# Multivibrator_2_0.net
KiCad netlist of a schematic drawn in EasyEDA
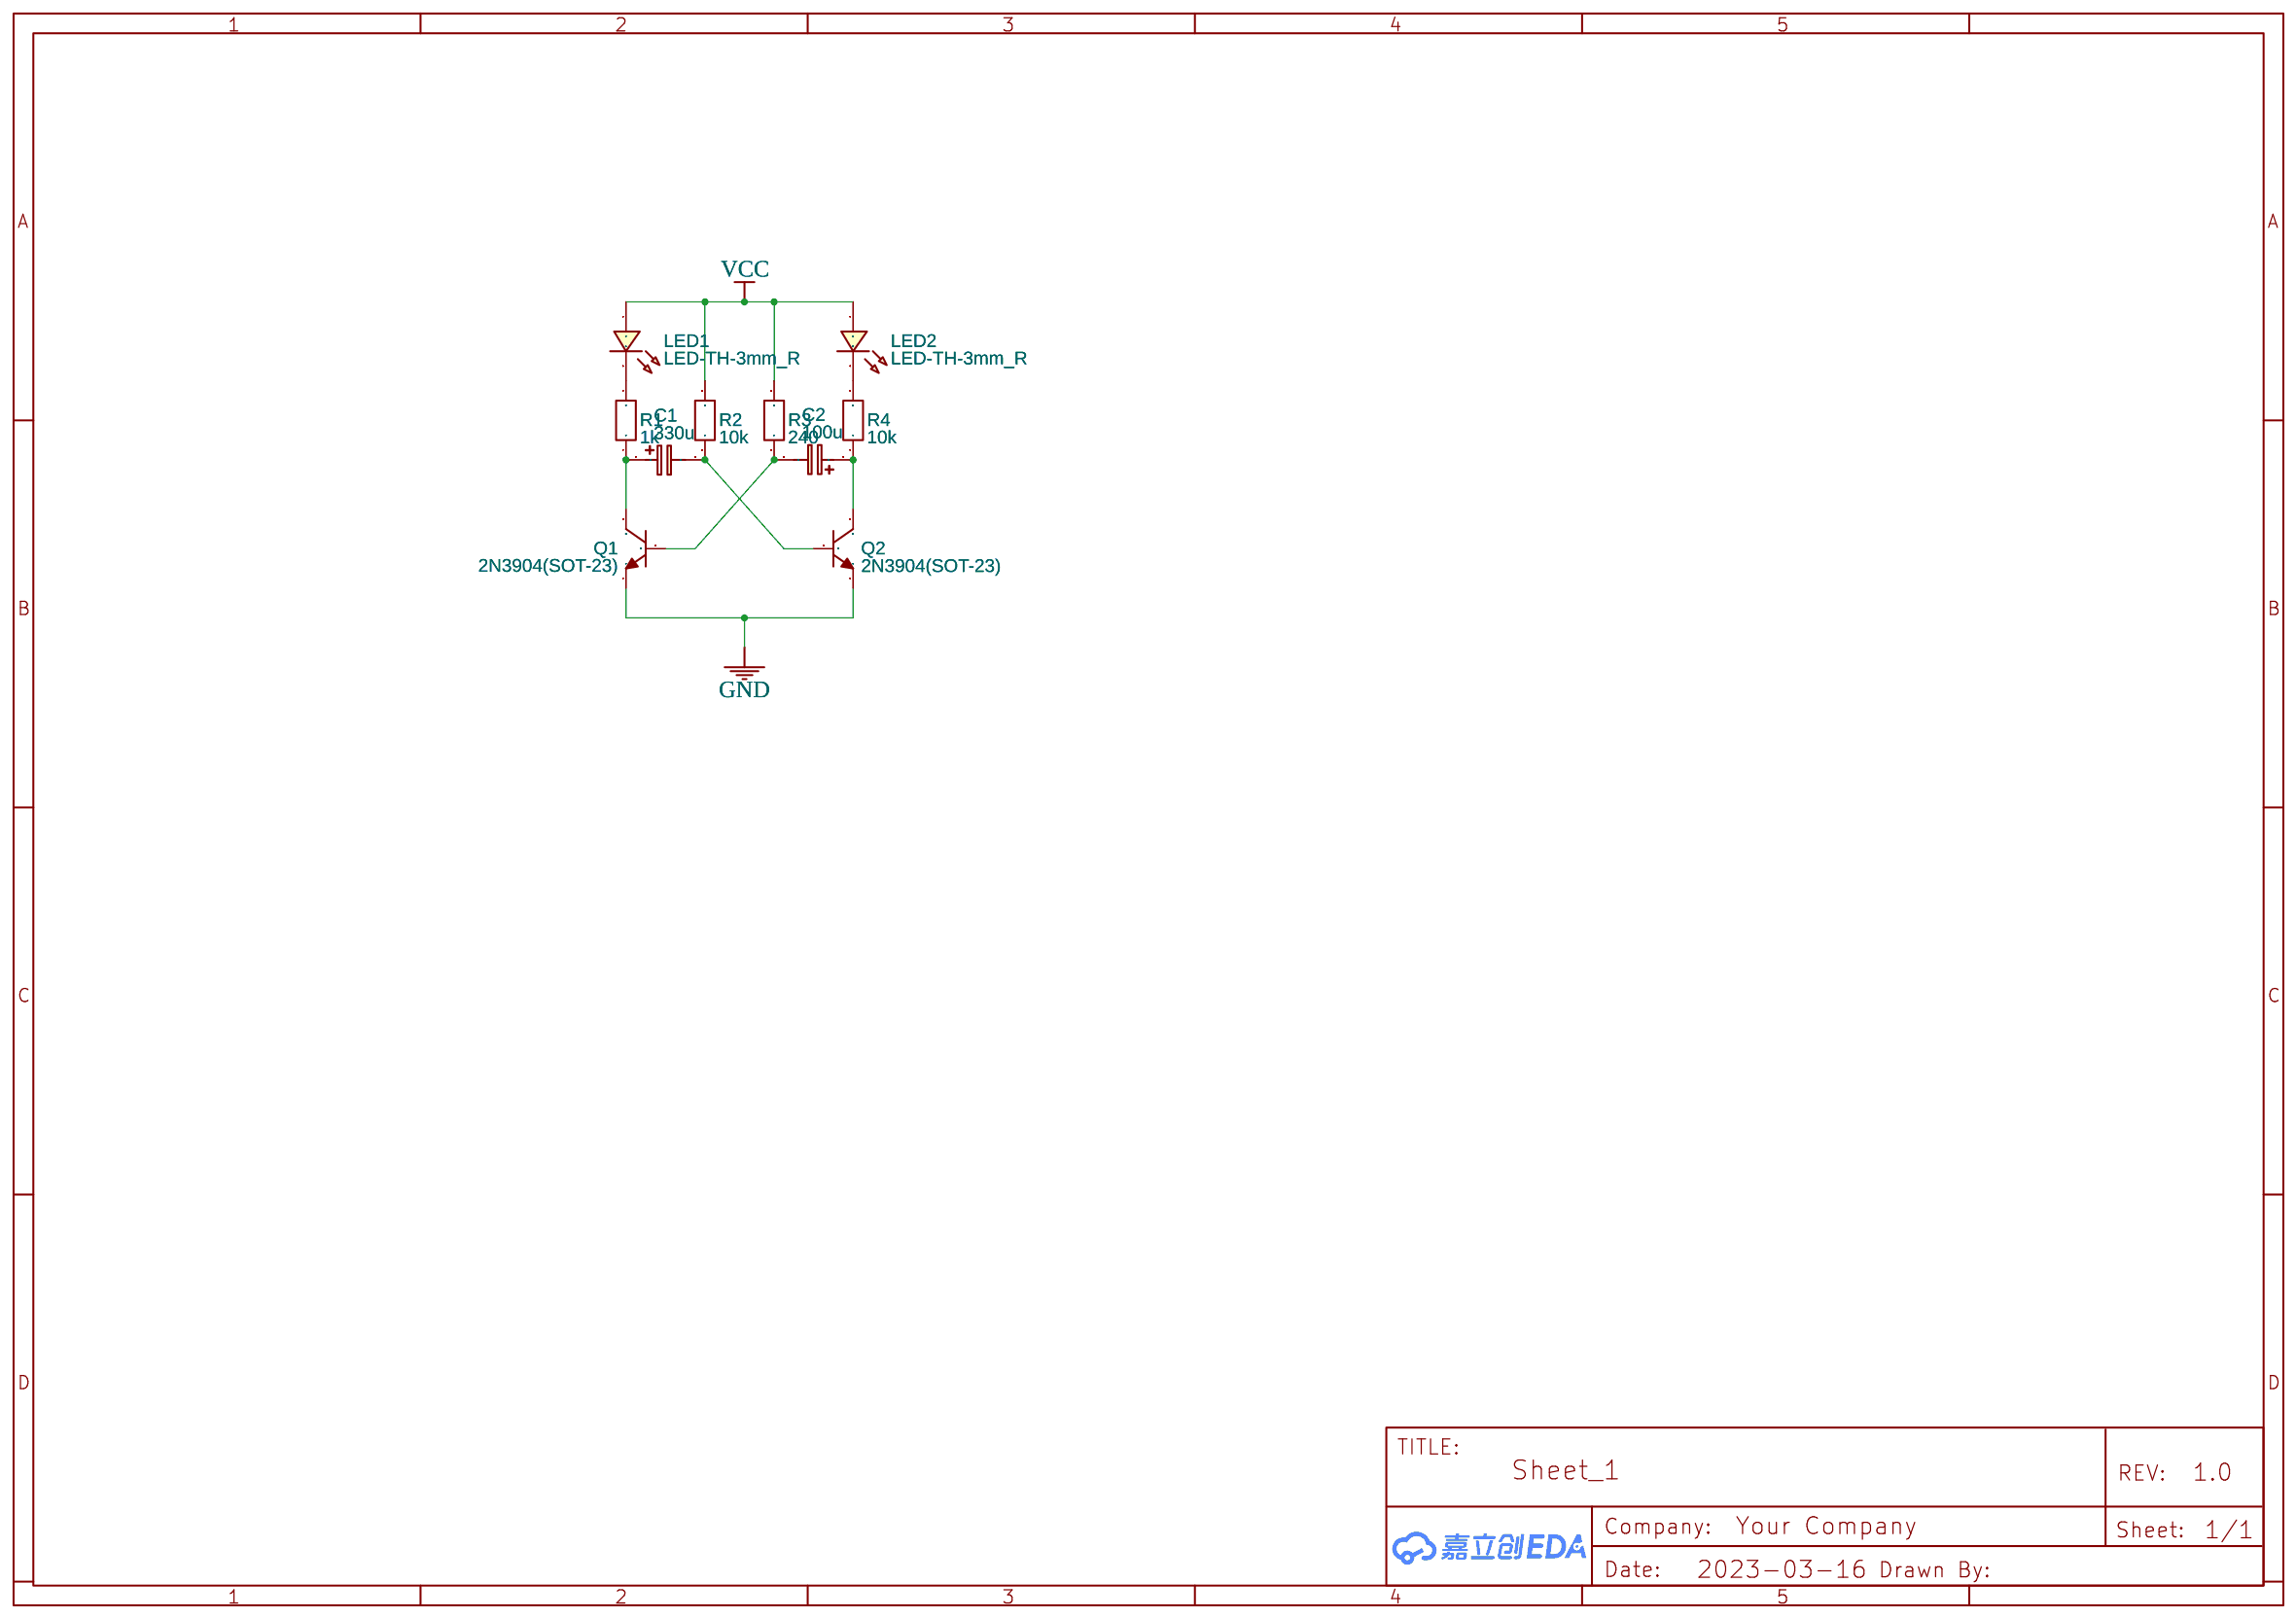
[diagram p0: schematic sheet]

(export (version "E")
  (design (tool "Eeschema 10.0.6"))
  (components
    (comp (ref "C1") (value "330u") (libsource (lib "") (part "CE_TH_D3.0×F1.5_EU")))
    (comp (ref "C2") (value "100u") (libsource (lib "") (part "CE_TH_D3.0×F1.5_EU_1")))
    (comp (ref "LED1")
      (value "LED-TH-3mm_R")
      (fields
        (field (name "BOM_Manufacturer Part") "204-10SDRD/S530-A3-L")
        (field (name "BOM_Supplier Part") "C84774")
      )
      (libsource (lib "") (part "LED-TH-3mm_R"))
    )
    (comp (ref "LED2")
      (value "LED-TH-3mm_R")
      (fields
        (field (name "BOM_Manufacturer Part") "204-10SDRD/S530-A3-L")
        (field (name "BOM_Supplier Part") "C84774")
      )
      (libsource (lib "") (part "LED-TH-3mm_R"))
    )
    (comp (ref "Q1")
      (value "2N3904(SOT-23)")
      (fields
        (field (name "BOM_Manufacturer Part") "2n3904S-RTK/PS")
        (field (name "BOM_Supplier Part") "C18536")
      )
      (libsource (lib "") (part "2N3904(SOT-23)"))
    )
    (comp (ref "Q2")
      (value "2N3904(SOT-23)")
      (fields
        (field (name "BOM_Manufacturer Part") "2n3904S-RTK/PS")
        (field (name "BOM_Supplier Part") "C18536")
      )
      (libsource (lib "") (part "2N3904(SOT-23)_1"))
    )
    (comp (ref "R1") (value "1k") (libsource (lib "") (part "R_AXIAL-0.3_EU")))
    (comp (ref "R2") (value "10k") (libsource (lib "") (part "R_AXIAL-0.3_EU")))
    (comp (ref "R3") (value "240") (libsource (lib "") (part "R_AXIAL-0.3_EU")))
    (comp (ref "R4") (value "10k") (libsource (lib "") (part "R_AXIAL-0.3_EU")))
  )
  (nets
    (net (code "1") (name "GND") (class "Default")
      (node (ref "Q1") (pin "1") (pinfunction "E_1") (pintype "input"))
      (node (ref "Q2") (pin "1") (pinfunction "E_1") (pintype "input"))
    )
    (net (code "2") (name "Net-(LED1-Pad2)") (class "Default")
      (node (ref "LED1") (pin "2") (pinfunction "2_2") (pintype "unspecified"))
      (node (ref "R1") (pin "2") (pinfunction "2_2") (pintype "unspecified"))
    )
    (net (code "3") (name "Net-(LED2-Pad2)") (class "Default")
      (node (ref "LED2") (pin "2") (pinfunction "2_2") (pintype "unspecified"))
      (node (ref "R4") (pin "2") (pinfunction "2_2") (pintype "unspecified"))
    )
    (net (code "4") (name "Net-(Q1-B)") (class "Default")
      (node (ref "C2") (pin "2") (pinfunction "2_2") (pintype "unspecified"))
      (node (ref "Q1") (pin "2") (pinfunction "B_2") (pintype "input"))
      (node (ref "R3") (pin "1") (pinfunction "1_1") (pintype "unspecified"))
    )
    (net (code "5") (name "Net-(Q1-C)") (class "Default")
      (node (ref "C1") (pin "1") (pinfunction "1_1") (pintype "unspecified"))
      (node (ref "Q1") (pin "3") (pinfunction "C_3") (pintype "input"))
      (node (ref "R1") (pin "1") (pinfunction "1_1") (pintype "unspecified"))
    )
    (net (code "6") (name "Net-(Q2-B)") (class "Default")
      (node (ref "C1") (pin "2") (pinfunction "2_2") (pintype "unspecified"))
      (node (ref "Q2") (pin "2") (pinfunction "B_2") (pintype "input"))
      (node (ref "R2") (pin "1") (pinfunction "1_1") (pintype "unspecified"))
    )
    (net (code "7") (name "Net-(Q2-C)") (class "Default")
      (node (ref "C2") (pin "1") (pinfunction "1_1") (pintype "unspecified"))
      (node (ref "Q2") (pin "3") (pinfunction "C_3") (pintype "input"))
      (node (ref "R4") (pin "1") (pinfunction "1_1") (pintype "unspecified"))
    )
    (net (code "8") (name "VCC") (class "Default")
      (node (ref "LED1") (pin "1") (pinfunction "1_1") (pintype "unspecified"))
      (node (ref "LED2") (pin "1") (pinfunction "1_1") (pintype "unspecified"))
      (node (ref "R2") (pin "2") (pinfunction "2_2") (pintype "unspecified"))
      (node (ref "R3") (pin "2") (pinfunction "2_2") (pintype "unspecified"))
    )
  )
)
